# openstepper.net
KiCad netlist of a schematic drawn in EAGLE
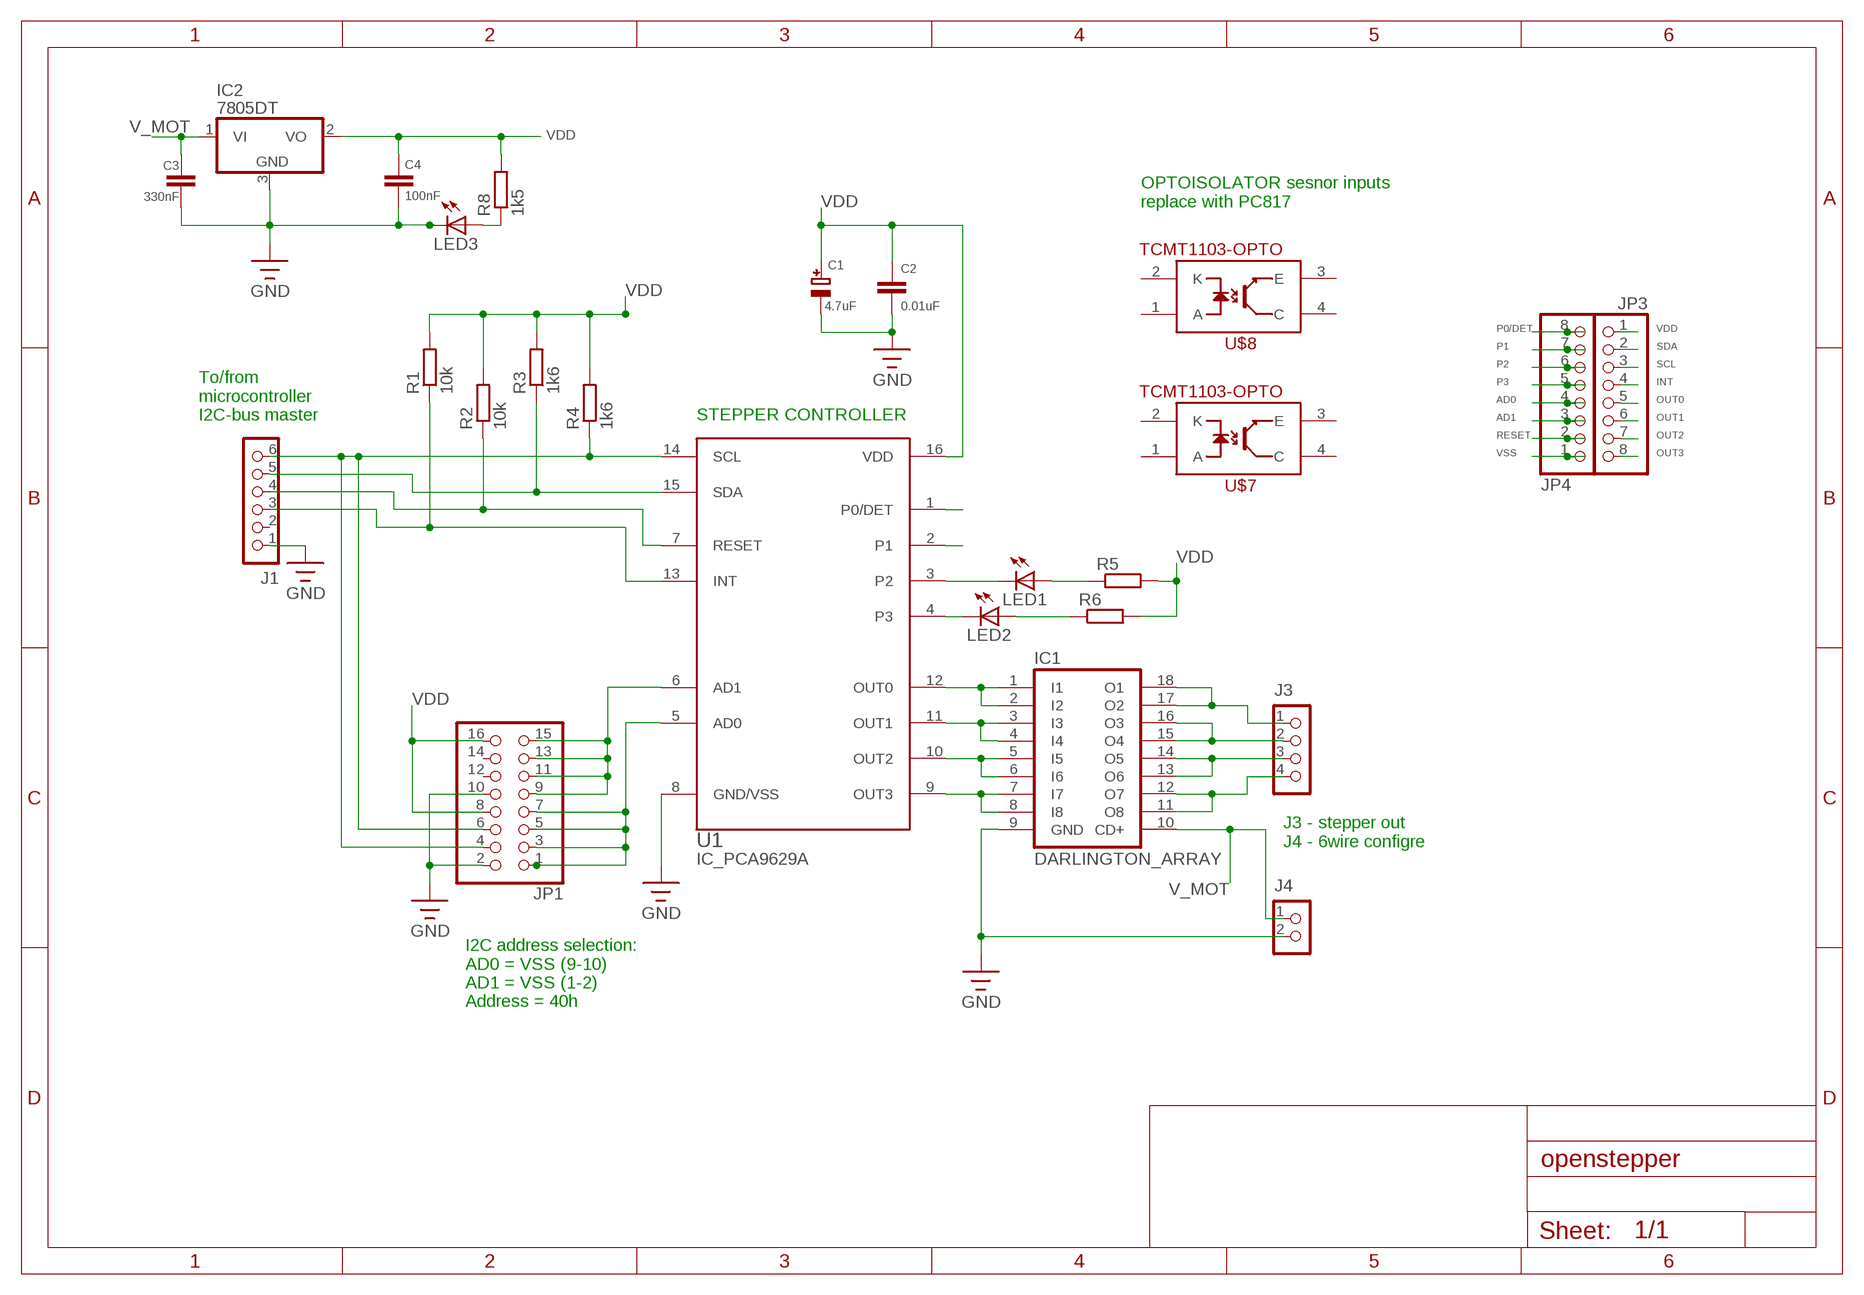
[diagram p0: schematic, sheet 1]

(export (version "E")
  (design (tool "Eeschema 10.0.6"))
  (components
    (comp (ref "C1")
      (value "4.7uF")
      (footprint "eagle-import:PANASONIC_C")
      (libsource (lib "eagle-import") (part "CAP_ELECTROLYTICPANASONIC_C"))
    )
    (comp (ref "C2")
      (value "0.01uF")
      (footprint "eagle-import:C805")
      (libsource (lib "eagle-import") (part "CAPACITOR_NPOL-0805"))
    )
    (comp (ref "C3")
      (value "330nF")
      (footprint "eagle-import:C025-024X044")
      (libsource (lib "eagle-import") (part "C-EU025-024X044"))
    )
    (comp (ref "C4")
      (value "100nF")
      (footprint "eagle-import:C025-024X044")
      (libsource (lib "eagle-import") (part "C-EU025-024X044"))
    )
    (comp (ref "IC1")
      (value "DARLINGTON_ARRAY")
      (footprint "eagle-import:SO-18")
      (libsource (lib "eagle-import") (part "IC_ULN2803A-SO-18"))
    )
    (comp (ref "IC2")
      (value "7805DT")
      (footprint "eagle-import:TO252")
      (libsource (lib "eagle-import") (part "78DT05"))
    )
    (comp (ref "J1")
      (value "CON_HEADER_1X06-PTH")
      (footprint "eagle-import:M1X6")
      (libsource (lib "eagle-import") (part "CON_HEADER_1X06-PTH"))
    )
    (comp (ref "J3")
      (value "CON_HEADER_1X04")
      (footprint "eagle-import:M1X4")
      (libsource (lib "eagle-import") (part "CON_HEADER_1X04"))
    )
    (comp (ref "J4")
      (value "CON_HEADER_1X02-PTH")
      (footprint "eagle-import:M1X2")
      (libsource (lib "eagle-import") (part "CON_HEADER_1X02-PTH"))
    )
    (comp (ref "JP1")
      (value "HEADER-2X8")
      (footprint "eagle-import:2X08")
      (libsource (lib "eagle-import") (part "HEADER-2X8"))
    )
    (comp (ref "JP3")
      (value "PINHD-1X8BIG")
      (footprint "eagle-import:1X08-BIG")
      (libsource (lib "eagle-import") (part "PINHD-1X8BIG"))
    )
    (comp (ref "JP4")
      (value "PINHD-1X8BIG")
      (footprint "eagle-import:1X08-BIG")
      (libsource (lib "eagle-import") (part "PINHD-1X8BIG"))
    )
    (comp (ref "LED1")
      (value "LED-0805")
      (footprint "eagle-import:LED-805")
      (libsource (lib "eagle-import") (part "LED-0805"))
    )
    (comp (ref "LED2")
      (value "LED-0805")
      (footprint "eagle-import:LED-805")
      (libsource (lib "eagle-import") (part "LED-0805"))
    )
    (comp (ref "LED3")
      (value "LED-0805")
      (footprint "eagle-import:LED-805")
      (libsource (lib "eagle-import") (part "LED-0805"))
    )
    (comp (ref "R1")
      (value "10k")
      (footprint "eagle-import:R1206")
      (libsource (lib "eagle-import") (part "RESISTOR-1206"))
    )
    (comp (ref "R2")
      (value "10k")
      (footprint "eagle-import:R1206")
      (libsource (lib "eagle-import") (part "RESISTOR-1206"))
    )
    (comp (ref "R3")
      (value "1k6")
      (footprint "eagle-import:R1206")
      (libsource (lib "eagle-import") (part "RESISTOR-1206"))
    )
    (comp (ref "R4")
      (value "1k6")
      (footprint "eagle-import:R1206")
      (libsource (lib "eagle-import") (part "RESISTOR-1206"))
    )
    (comp (ref "R5")
      (value "RESISTORR805-0805")
      (footprint "eagle-import:R805")
      (libsource (lib "eagle-import") (part "RESISTOR-0805R805"))
    )
    (comp (ref "R6")
      (value "RESISTORR805-0805")
      (footprint "eagle-import:R805")
      (libsource (lib "eagle-import") (part "RESISTOR-0805R805"))
    )
    (comp (ref "R8")
      (value "1k5")
      (footprint "eagle-import:R1206")
      (libsource (lib "eagle-import") (part "RESISTOR-1206"))
    )
    (comp (ref "U$7")
      (value "TCMT1103-OPTO")
      (footprint "eagle-import:SSOP-4")
      (libsource (lib "eagle-import") (part "TCMT1103-OPTO"))
    )
    (comp (ref "U$8")
      (value "TCMT1103-OPTO")
      (footprint "eagle-import:SSOP-4")
      (libsource (lib "eagle-import") (part "TCMT1103-OPTO"))
    )
    (comp (ref "U1")
      (value "IC_PCA9629A")
      (footprint "eagle-import:TSSOP-16")
      (libsource (lib "eagle-import") (part "IC_PCA9629A"))
    )
  )
  (nets
    (net (code "1") (name "/AD0") (class "Default")
      (node (ref "JP1") (pin "1") (pinfunction "1_1") (pintype "passive"))
      (node (ref "JP1") (pin "3") (pinfunction "3_3") (pintype "passive"))
      (node (ref "JP1") (pin "5") (pinfunction "5_5") (pintype "passive"))
      (node (ref "JP1") (pin "7") (pinfunction "7_7") (pintype "passive"))
      (node (ref "JP4") (pin "4") (pinfunction "4_4") (pintype "passive"))
      (node (ref "U1") (pin "5") (pinfunction "AD0_5") (pintype "bidirectional"))
    )
    (net (code "2") (name "/AD1") (class "Default")
      (node (ref "JP1") (pin "11") (pinfunction "11_11") (pintype "passive"))
      (node (ref "JP1") (pin "13") (pinfunction "13_13") (pintype "passive"))
      (node (ref "JP1") (pin "15") (pinfunction "15_15") (pintype "passive"))
      (node (ref "JP1") (pin "9") (pinfunction "9_9") (pintype "passive"))
      (node (ref "JP4") (pin "3") (pinfunction "3_3") (pintype "passive"))
      (node (ref "U1") (pin "6") (pinfunction "AD1_6") (pintype "bidirectional"))
    )
    (net (code "3") (name "/INT") (class "Default")
      (node (ref "J1") (pin "3") (pinfunction "3_3") (pintype "passive"))
      (node (ref "JP3") (pin "4") (pinfunction "4_4") (pintype "passive"))
      (node (ref "R1") (pin "1") (pinfunction "1_1") (pintype "passive"))
      (node (ref "U1") (pin "13") (pinfunction "INT_13") (pintype "bidirectional"))
    )
    (net (code "4") (name "/OUT0") (class "Default")
      (node (ref "IC1") (pin "1") (pinfunction "I1_1") (pintype "input"))
      (node (ref "IC1") (pin "2") (pinfunction "I2_2") (pintype "input"))
      (node (ref "JP3") (pin "5") (pinfunction "5_5") (pintype "passive"))
      (node (ref "U1") (pin "12") (pinfunction "OUT0_12") (pintype "bidirectional"))
    )
    (net (code "5") (name "/OUT1") (class "Default")
      (node (ref "IC1") (pin "3") (pinfunction "I3_3") (pintype "input"))
      (node (ref "IC1") (pin "4") (pinfunction "I4_4") (pintype "input"))
      (node (ref "JP3") (pin "6") (pinfunction "6_6") (pintype "passive"))
      (node (ref "U1") (pin "11") (pinfunction "OUT1_11") (pintype "bidirectional"))
    )
    (net (code "6") (name "/OUT2") (class "Default")
      (node (ref "IC1") (pin "5") (pinfunction "I5_5") (pintype "input"))
      (node (ref "IC1") (pin "6") (pinfunction "I6_6") (pintype "input"))
      (node (ref "JP3") (pin "7") (pinfunction "7_7") (pintype "passive"))
      (node (ref "U1") (pin "10") (pinfunction "OUT2_10") (pintype "bidirectional"))
    )
    (net (code "7") (name "/OUT3") (class "Default")
      (node (ref "IC1") (pin "7") (pinfunction "I7_7") (pintype "input"))
      (node (ref "IC1") (pin "8") (pinfunction "I8_8") (pintype "input"))
      (node (ref "JP3") (pin "8") (pinfunction "8_8") (pintype "passive"))
      (node (ref "U1") (pin "9") (pinfunction "OUT3_9") (pintype "bidirectional"))
    )
    (net (code "8") (name "/P0{slash}DET") (class "Default")
      (node (ref "JP4") (pin "8") (pinfunction "8_8") (pintype "passive"))
      (node (ref "U1") (pin "1") (pinfunction "P0/DET_1") (pintype "bidirectional"))
    )
    (net (code "9") (name "/P1") (class "Default")
      (node (ref "JP4") (pin "7") (pinfunction "7_7") (pintype "passive"))
      (node (ref "U1") (pin "2") (pinfunction "P1_2") (pintype "bidirectional"))
    )
    (net (code "10") (name "/P2") (class "Default")
      (node (ref "JP4") (pin "6") (pinfunction "6_6") (pintype "passive"))
      (node (ref "LED1") (pin "C") (pinfunction "C_C") (pintype "passive"))
      (node (ref "U1") (pin "3") (pinfunction "P2_3") (pintype "bidirectional"))
    )
    (net (code "11") (name "/P3") (class "Default")
      (node (ref "JP4") (pin "5") (pinfunction "5_5") (pintype "passive"))
      (node (ref "LED2") (pin "C") (pinfunction "C_C") (pintype "passive"))
      (node (ref "U1") (pin "4") (pinfunction "P3_4") (pintype "bidirectional"))
    )
    (net (code "12") (name "/RESET") (class "Default")
      (node (ref "J1") (pin "4") (pinfunction "4_4") (pintype "passive"))
      (node (ref "JP4") (pin "2") (pinfunction "2_2") (pintype "passive"))
      (node (ref "R2") (pin "1") (pinfunction "1_1") (pintype "passive"))
      (node (ref "U1") (pin "7") (pinfunction "RESET_7") (pintype "bidirectional"))
    )
    (net (code "13") (name "/SCL") (class "Default")
      (node (ref "J1") (pin "6") (pinfunction "6_6") (pintype "passive"))
      (node (ref "JP1") (pin "4") (pinfunction "4_4") (pintype "passive"))
      (node (ref "JP1") (pin "6") (pinfunction "6_6") (pintype "passive"))
      (node (ref "JP3") (pin "3") (pinfunction "3_3") (pintype "passive"))
      (node (ref "R4") (pin "1") (pinfunction "1_1") (pintype "passive"))
      (node (ref "U1") (pin "14") (pinfunction "SCL_14") (pintype "bidirectional"))
    )
    (net (code "14") (name "/SDA") (class "Default")
      (node (ref "J1") (pin "5") (pinfunction "5_5") (pintype "passive"))
      (node (ref "JP3") (pin "2") (pinfunction "2_2") (pintype "passive"))
      (node (ref "R3") (pin "1") (pinfunction "1_1") (pintype "passive"))
      (node (ref "U1") (pin "15") (pinfunction "SDA_15") (pintype "bidirectional"))
    )
    (net (code "15") (name "/VDD") (class "Default")
      (node (ref "C1") (pin "+") (pinfunction "+_+") (pintype "passive"))
      (node (ref "C2") (pin "1") (pinfunction "1_1") (pintype "passive"))
      (node (ref "C4") (pin "2") (pinfunction "2_2") (pintype "passive"))
      (node (ref "IC2") (pin "2") (pinfunction "VO_2") (pintype "passive"))
      (node (ref "JP1") (pin "16") (pinfunction "16_16") (pintype "passive"))
      (node (ref "JP1") (pin "8") (pinfunction "8_8") (pintype "passive"))
      (node (ref "JP3") (pin "1") (pinfunction "1_1") (pintype "passive"))
      (node (ref "R1") (pin "2") (pinfunction "2_2") (pintype "passive"))
      (node (ref "R2") (pin "2") (pinfunction "2_2") (pintype "passive"))
      (node (ref "R3") (pin "2") (pinfunction "2_2") (pintype "passive"))
      (node (ref "R4") (pin "2") (pinfunction "2_2") (pintype "passive"))
      (node (ref "R5") (pin "2") (pinfunction "2_2") (pintype "passive"))
      (node (ref "R6") (pin "2") (pinfunction "2_2") (pintype "passive"))
      (node (ref "R8") (pin "2") (pinfunction "2_2") (pintype "passive"))
      (node (ref "U1") (pin "16") (pinfunction "VDD_16") (pintype "bidirectional"))
    )
    (net (code "16") (name "/VSS") (class "Default")
      (node (ref "JP4") (pin "1") (pinfunction "1_1") (pintype "passive"))
    )
    (net (code "17") (name "/V_MOT") (class "Default")
      (node (ref "C3") (pin "2") (pinfunction "2_2") (pintype "passive"))
      (node (ref "IC1") (pin "10") (pinfunction "CD+_10") (pintype "passive"))
      (node (ref "IC2") (pin "1") (pinfunction "VI_1") (pintype "input"))
      (node (ref "J4") (pin "1") (pinfunction "1_1") (pintype "passive"))
    )
    (net (code "18") (name "GND") (class "Default")
      (node (ref "C1") (pin "-") (pinfunction "-_-") (pintype "passive"))
      (node (ref "C2") (pin "2") (pinfunction "2_2") (pintype "passive"))
      (node (ref "C3") (pin "1") (pinfunction "1_1") (pintype "passive"))
      (node (ref "C4") (pin "1") (pinfunction "1_1") (pintype "passive"))
      (node (ref "IC1") (pin "9") (pinfunction "GND_9") (pintype "power_in"))
      (node (ref "IC2") (pin "3") (pinfunction "GND_3") (pintype "passive"))
      (node (ref "J1") (pin "1") (pinfunction "1_1") (pintype "bidirectional"))
      (node (ref "J4") (pin "2") (pinfunction "2_2") (pintype "passive"))
      (node (ref "JP1") (pin "10") (pinfunction "10_10") (pintype "passive"))
      (node (ref "JP1") (pin "2") (pinfunction "2_2") (pintype "passive"))
      (node (ref "LED3") (pin "C") (pinfunction "C_C") (pintype "passive"))
      (node (ref "U1") (pin "8") (pinfunction "GND/VSS_8") (pintype "bidirectional"))
    )
    (net (code "19") (name "Net-(IC1-O1)") (class "Default")
      (node (ref "IC1") (pin "17") (pinfunction "O2_17") (pintype "open_collector"))
      (node (ref "IC1") (pin "18") (pinfunction "O1_18") (pintype "open_collector"))
      (node (ref "J3") (pin "1") (pinfunction "1_1") (pintype "bidirectional"))
    )
    (net (code "20") (name "Net-(IC1-O3)") (class "Default")
      (node (ref "IC1") (pin "15") (pinfunction "O4_15") (pintype "open_collector"))
      (node (ref "IC1") (pin "16") (pinfunction "O3_16") (pintype "open_collector"))
      (node (ref "J3") (pin "2") (pinfunction "2_2") (pintype "bidirectional"))
    )
    (net (code "21") (name "Net-(IC1-O5)") (class "Default")
      (node (ref "IC1") (pin "13") (pinfunction "O6_13") (pintype "open_collector"))
      (node (ref "IC1") (pin "14") (pinfunction "O5_14") (pintype "open_collector"))
      (node (ref "J3") (pin "3") (pinfunction "3_3") (pintype "bidirectional"))
    )
    (net (code "22") (name "Net-(IC1-O7)") (class "Default")
      (node (ref "IC1") (pin "11") (pinfunction "O8_11") (pintype "open_collector"))
      (node (ref "IC1") (pin "12") (pinfunction "O7_12") (pintype "open_collector"))
      (node (ref "J3") (pin "4") (pinfunction "4_4") (pintype "bidirectional"))
    )
    (net (code "23") (name "Net-(LED1-PadA)") (class "Default")
      (node (ref "LED1") (pin "A") (pinfunction "A_A") (pintype "passive"))
      (node (ref "R5") (pin "1") (pinfunction "1_1") (pintype "passive"))
    )
    (net (code "24") (name "Net-(LED2-PadA)") (class "Default")
      (node (ref "LED2") (pin "A") (pinfunction "A_A") (pintype "passive"))
      (node (ref "R6") (pin "1") (pinfunction "1_1") (pintype "passive"))
    )
    (net (code "25") (name "Net-(LED3-PadA)") (class "Default")
      (node (ref "LED3") (pin "A") (pinfunction "A_A") (pintype "passive"))
      (node (ref "R8") (pin "1") (pinfunction "1_1") (pintype "passive"))
    )
    (net (code "26") (name "unconnected-(J1-Pad2)") (class "Default")
      (node (ref "J1") (pin "2") (pinfunction "2_2") (pintype "bidirectional"))
    )
    (net (code "27") (name "unconnected-(JP1-Pad12)") (class "Default")
      (node (ref "JP1") (pin "12") (pinfunction "12_12") (pintype "passive"))
    )
    (net (code "28") (name "unconnected-(JP1-Pad14)") (class "Default")
      (node (ref "JP1") (pin "14") (pinfunction "14_14") (pintype "passive"))
    )
    (net (code "29") (name "unconnected-(U$7-A-Pad1)") (class "Default")
      (node (ref "U$7") (pin "1") (pinfunction "A_1") (pintype "bidirectional"))
    )
    (net (code "30") (name "unconnected-(U$7-C-Pad4)") (class "Default")
      (node (ref "U$7") (pin "4") (pinfunction "C_4") (pintype "bidirectional"))
    )
    (net (code "31") (name "unconnected-(U$7-E-Pad3)") (class "Default")
      (node (ref "U$7") (pin "3") (pinfunction "E_3") (pintype "bidirectional"))
    )
    (net (code "32") (name "unconnected-(U$7-K-Pad2)") (class "Default")
      (node (ref "U$7") (pin "2") (pinfunction "K_2") (pintype "bidirectional"))
    )
    (net (code "33") (name "unconnected-(U$8-A-Pad1)") (class "Default")
      (node (ref "U$8") (pin "1") (pinfunction "A_1") (pintype "bidirectional"))
    )
    (net (code "34") (name "unconnected-(U$8-C-Pad4)") (class "Default")
      (node (ref "U$8") (pin "4") (pinfunction "C_4") (pintype "bidirectional"))
    )
    (net (code "35") (name "unconnected-(U$8-E-Pad3)") (class "Default")
      (node (ref "U$8") (pin "3") (pinfunction "E_3") (pintype "bidirectional"))
    )
    (net (code "36") (name "unconnected-(U$8-K-Pad2)") (class "Default")
      (node (ref "U$8") (pin "2") (pinfunction "K_2") (pintype "bidirectional"))
    )
  )
)
